# Sheet1.net
KiCad netlist of a schematic drawn in Altium Designer
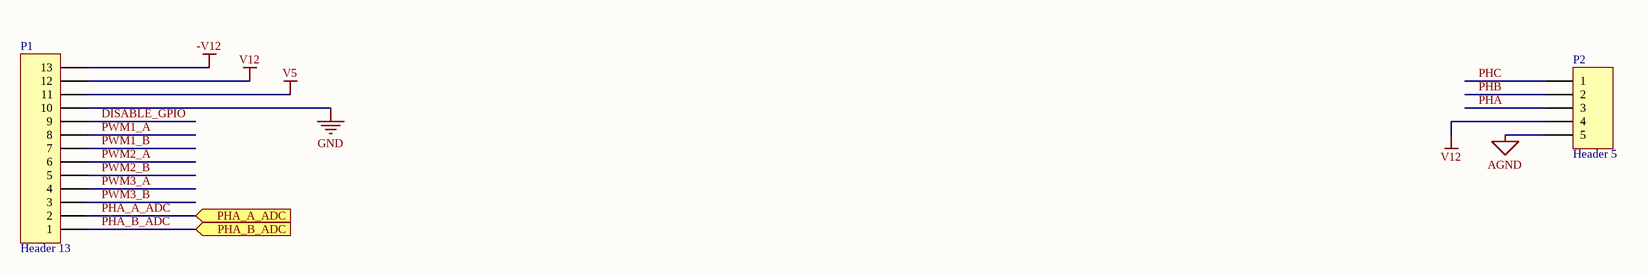
[diagram p0: Sheet1.SchDoc]

(export (version "E")
  (design (tool "Eeschema 10.0.6"))
  (components
    (comp (ref "P1")
      (value "Header 13")
      (footprint "HDR1X13")
      (description "Header, 13-Pin")
      (fields (field (name "PUBLISHER") "Altium Limited"))
      (libsource (lib "Miscellaneous Connectors") (part "Header 13"))
    )
    (comp (ref "P2")
      (value "Header 5")
      (footprint "HDR1X5")
      (description "Header, 5-Pin")
      (fields (field (name "PUBLISHER") "Altium Limited"))
      (libsource (lib "Miscellaneous Connectors") (part "Header 5"))
    )
  )
  (nets
    (net (code "1") (name "-V12") (class "Default")
      (node (ref "P1") (pin "13") (pinfunction "13_13") (pintype "passive"))
    )
    (net (code "2") (name "/DISABLE_GPIO") (class "Default")
      (node (ref "P1") (pin "9") (pinfunction "9_9") (pintype "passive"))
    )
    (net (code "3") (name "/PHA") (class "Default")
      (node (ref "P2") (pin "3") (pinfunction "3_3") (pintype "passive"))
    )
    (net (code "4") (name "/PHA_A_ADC") (class "Default")
      (node (ref "P1") (pin "2") (pinfunction "2_2") (pintype "passive"))
    )
    (net (code "5") (name "/PHA_B_ADC") (class "Default")
      (node (ref "P1") (pin "1") (pinfunction "1_1") (pintype "passive"))
    )
    (net (code "6") (name "/PHB") (class "Default")
      (node (ref "P2") (pin "2") (pinfunction "2_2") (pintype "passive"))
    )
    (net (code "7") (name "/PHC") (class "Default")
      (node (ref "P2") (pin "1") (pinfunction "1_1") (pintype "passive"))
    )
    (net (code "8") (name "/PWM1_A") (class "Default")
      (node (ref "P1") (pin "8") (pinfunction "8_8") (pintype "passive"))
    )
    (net (code "9") (name "/PWM1_B") (class "Default")
      (node (ref "P1") (pin "7") (pinfunction "7_7") (pintype "passive"))
    )
    (net (code "10") (name "/PWM2_A") (class "Default")
      (node (ref "P1") (pin "6") (pinfunction "6_6") (pintype "passive"))
    )
    (net (code "11") (name "/PWM2_B") (class "Default")
      (node (ref "P1") (pin "5") (pinfunction "5_5") (pintype "passive"))
    )
    (net (code "12") (name "/PWM3_A") (class "Default")
      (node (ref "P1") (pin "4") (pinfunction "4_4") (pintype "passive"))
    )
    (net (code "13") (name "/PWM3_B") (class "Default")
      (node (ref "P1") (pin "3") (pinfunction "3_3") (pintype "passive"))
    )
    (net (code "14") (name "AGND") (class "Default")
      (node (ref "P2") (pin "5") (pinfunction "5_5") (pintype "passive"))
    )
    (net (code "15") (name "GND") (class "Default")
      (node (ref "P1") (pin "10") (pinfunction "10_10") (pintype "passive"))
    )
    (net (code "16") (name "V5") (class "Default")
      (node (ref "P1") (pin "11") (pinfunction "11_11") (pintype "passive"))
    )
    (net (code "17") (name "V12") (class "Default")
      (node (ref "P1") (pin "12") (pinfunction "12_12") (pintype "passive"))
      (node (ref "P2") (pin "4") (pinfunction "4_4") (pintype "passive"))
    )
  )
)
